# defi_schutz.net
KiCad netlist of a schematic drawn in EAGLE
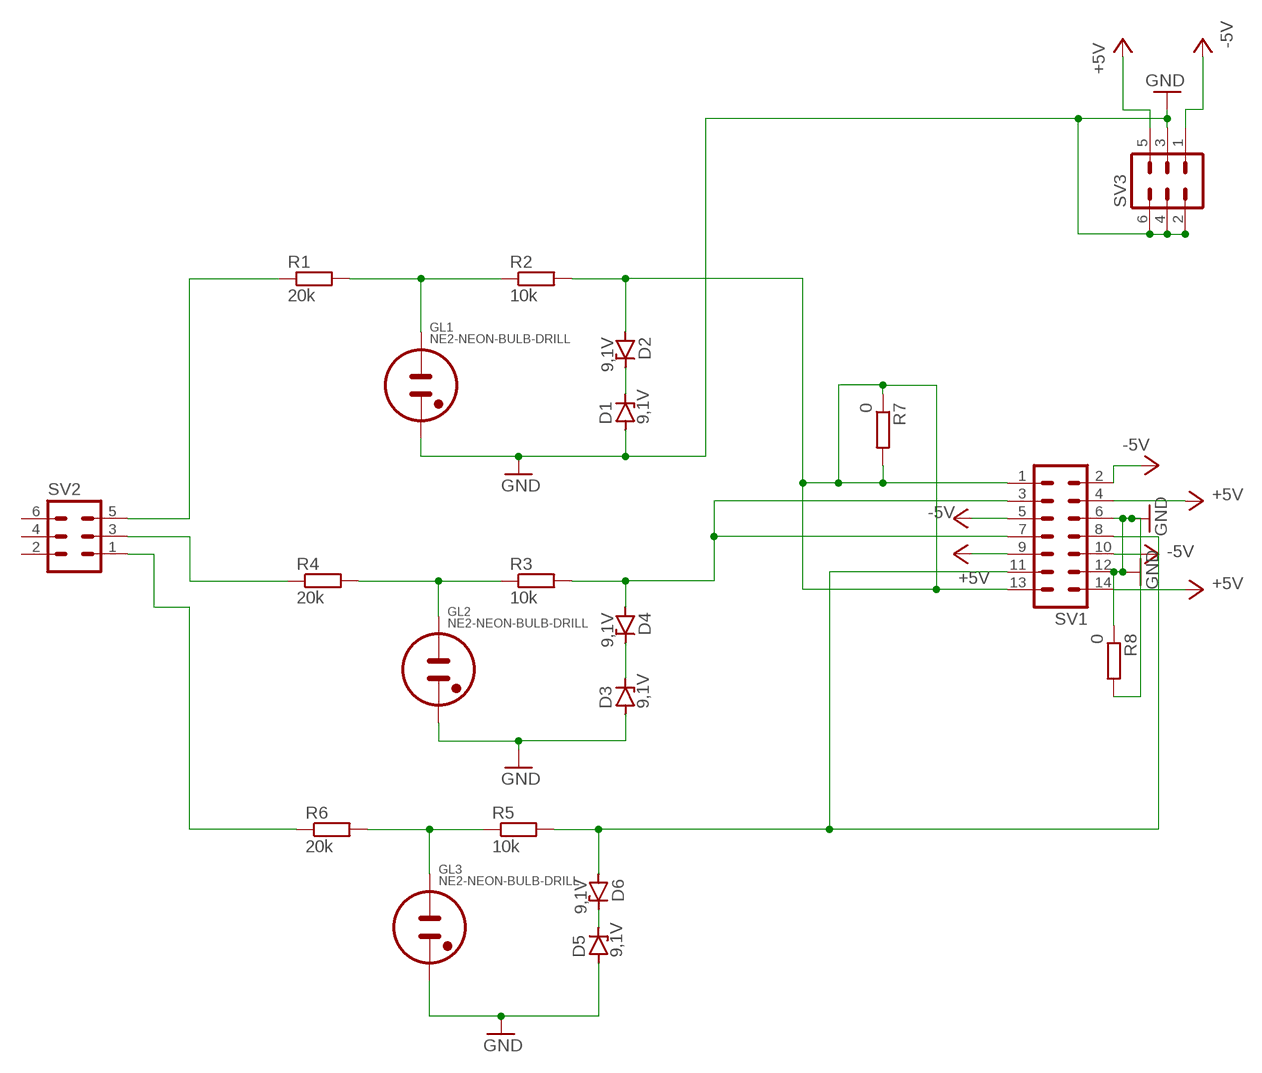
[diagram p0: schematic, sheet 1]

(export (version "E")
  (design (tool "Eeschema 10.0.6"))
  (components
    (comp (ref "D1")
      (value "9,1V")
      (footprint "eagle-import:DO41Z10")
      (libsource (lib "eagle-import") (part "1N4728"))
    )
    (comp (ref "D2")
      (value "9,1V")
      (footprint "eagle-import:DO41Z10")
      (libsource (lib "eagle-import") (part "1N4728"))
    )
    (comp (ref "D3")
      (value "9,1V")
      (footprint "eagle-import:DO41Z10")
      (libsource (lib "eagle-import") (part "1N4728"))
    )
    (comp (ref "D4")
      (value "9,1V")
      (footprint "eagle-import:DO41Z10")
      (libsource (lib "eagle-import") (part "1N4728"))
    )
    (comp (ref "D5")
      (value "9,1V")
      (footprint "eagle-import:DO41Z10")
      (libsource (lib "eagle-import") (part "1N4728"))
    )
    (comp (ref "D6")
      (value "9,1V")
      (footprint "eagle-import:DO41Z10")
      (libsource (lib "eagle-import") (part "1N4728"))
    )
    (comp (ref "GL1")
      (value "NE2-NEON-BULB-DRILL")
      (footprint "eagle-import:NE2-NEON-BULB-DRILL")
      (libsource (lib "eagle-import") (part "NE2-NEON-BULB-DRILL"))
    )
    (comp (ref "GL2")
      (value "NE2-NEON-BULB-DRILL")
      (footprint "eagle-import:NE2-NEON-BULB-DRILL")
      (libsource (lib "eagle-import") (part "NE2-NEON-BULB-DRILL"))
    )
    (comp (ref "GL3")
      (value "NE2-NEON-BULB-DRILL")
      (footprint "eagle-import:NE2-NEON-BULB-DRILL")
      (libsource (lib "eagle-import") (part "NE2-NEON-BULB-DRILL"))
    )
    (comp (ref "R1")
      (value "20k")
      (footprint "eagle-import:0207_10")
      (libsource (lib "eagle-import") (part "R-EU_0207/10"))
    )
    (comp (ref "R2")
      (value "10k")
      (footprint "eagle-import:0207_10")
      (libsource (lib "eagle-import") (part "R-EU_0207/10"))
    )
    (comp (ref "R3")
      (value "10k")
      (footprint "eagle-import:0207_10")
      (libsource (lib "eagle-import") (part "R-EU_0207/10"))
    )
    (comp (ref "R4")
      (value "20k")
      (footprint "eagle-import:0207_10")
      (libsource (lib "eagle-import") (part "R-EU_0207/10"))
    )
    (comp (ref "R5")
      (value "10k")
      (footprint "eagle-import:0207_10")
      (libsource (lib "eagle-import") (part "R-EU_0207/10"))
    )
    (comp (ref "R6")
      (value "20k")
      (footprint "eagle-import:0207_10")
      (libsource (lib "eagle-import") (part "R-EU_0207/10"))
    )
    (comp (ref "R7")
      (value "0")
      (footprint "eagle-import:0207_15")
      (libsource (lib "eagle-import") (part "R-EU_0207/15"))
    )
    (comp (ref "R8")
      (value "0")
      (footprint "eagle-import:0207_15")
      (libsource (lib "eagle-import") (part "R-EU_0207/15"))
    )
    (comp (ref "SV1")
      (value "ML14L")
      (footprint "eagle-import:ML14L")
      (libsource (lib "eagle-import") (part "ML14L"))
    )
    (comp (ref "SV2")
      (value "ML6L")
      (footprint "eagle-import:ML6L")
      (libsource (lib "eagle-import") (part "ML6L"))
    )
    (comp (ref "SV3")
      (value "ML6L")
      (footprint "eagle-import:ML6L")
      (libsource (lib "eagle-import") (part "ML6L"))
    )
  )
  (nets
    (net (code "1") (name "+5V") (class "Default")
      (node (ref "SV1") (pin "14") (pinfunction "14_14") (pintype "passive"))
      (node (ref "SV1") (pin "4") (pinfunction "4_4") (pintype "passive"))
      (node (ref "SV1") (pin "9") (pinfunction "9_9") (pintype "passive"))
      (node (ref "SV3") (pin "5") (pinfunction "5_5") (pintype "passive"))
    )
    (net (code "2") (name "-5V") (class "Default")
      (node (ref "SV1") (pin "10") (pinfunction "10_10") (pintype "passive"))
      (node (ref "SV1") (pin "2") (pinfunction "2_2") (pintype "passive"))
      (node (ref "SV1") (pin "5") (pinfunction "5_5") (pintype "passive"))
      (node (ref "SV3") (pin "1") (pinfunction "1_1") (pintype "passive"))
    )
    (net (code "3") (name "GND") (class "Default")
      (node (ref "D1") (pin "A") (pinfunction "A_A") (pintype "passive"))
      (node (ref "D3") (pin "A") (pinfunction "A_A") (pintype "passive"))
      (node (ref "D5") (pin "A") (pinfunction "A_A") (pintype "passive"))
      (node (ref "GL1") (pin "2") (pinfunction "A1_2") (pintype "passive"))
      (node (ref "GL2") (pin "2") (pinfunction "A1_2") (pintype "passive"))
      (node (ref "GL3") (pin "2") (pinfunction "A1_2") (pintype "passive"))
      (node (ref "R8") (pin "1") (pinfunction "1_1") (pintype "passive"))
      (node (ref "R8") (pin "2") (pinfunction "2_2") (pintype "passive"))
      (node (ref "SV1") (pin "12") (pinfunction "12_12") (pintype "passive"))
      (node (ref "SV1") (pin "6") (pinfunction "6_6") (pintype "passive"))
      (node (ref "SV3") (pin "2") (pinfunction "2_2") (pintype "passive"))
      (node (ref "SV3") (pin "3") (pinfunction "3_3") (pintype "passive"))
      (node (ref "SV3") (pin "4") (pinfunction "4_4") (pintype "passive"))
      (node (ref "SV3") (pin "6") (pinfunction "6_6") (pintype "passive"))
    )
    (net (code "4") (name "Net-(D1-PadC)") (class "Default")
      (node (ref "D1") (pin "C") (pinfunction "C_C") (pintype "passive"))
      (node (ref "D2") (pin "C") (pinfunction "C_C") (pintype "passive"))
    )
    (net (code "5") (name "Net-(D2-PadA)") (class "Default")
      (node (ref "D2") (pin "A") (pinfunction "A_A") (pintype "passive"))
      (node (ref "R2") (pin "2") (pinfunction "2_2") (pintype "passive"))
      (node (ref "R7") (pin "1") (pinfunction "1_1") (pintype "passive"))
      (node (ref "R7") (pin "2") (pinfunction "2_2") (pintype "passive"))
      (node (ref "SV1") (pin "1") (pinfunction "1_1") (pintype "passive"))
      (node (ref "SV1") (pin "13") (pinfunction "13_13") (pintype "passive"))
    )
    (net (code "6") (name "Net-(D3-PadC)") (class "Default")
      (node (ref "D3") (pin "C") (pinfunction "C_C") (pintype "passive"))
      (node (ref "D4") (pin "C") (pinfunction "C_C") (pintype "passive"))
    )
    (net (code "7") (name "Net-(D4-PadA)") (class "Default")
      (node (ref "D4") (pin "A") (pinfunction "A_A") (pintype "passive"))
      (node (ref "R3") (pin "2") (pinfunction "2_2") (pintype "passive"))
      (node (ref "SV1") (pin "3") (pinfunction "3_3") (pintype "passive"))
      (node (ref "SV1") (pin "7") (pinfunction "7_7") (pintype "passive"))
    )
    (net (code "8") (name "Net-(D5-PadC)") (class "Default")
      (node (ref "D5") (pin "C") (pinfunction "C_C") (pintype "passive"))
      (node (ref "D6") (pin "C") (pinfunction "C_C") (pintype "passive"))
    )
    (net (code "9") (name "Net-(D6-PadA)") (class "Default")
      (node (ref "D6") (pin "A") (pinfunction "A_A") (pintype "passive"))
      (node (ref "R5") (pin "2") (pinfunction "2_2") (pintype "passive"))
      (node (ref "SV1") (pin "11") (pinfunction "11_11") (pintype "passive"))
      (node (ref "SV1") (pin "8") (pinfunction "8_8") (pintype "passive"))
    )
    (net (code "10") (name "Net-(GL1-A)") (class "Default")
      (node (ref "GL1") (pin "1") (pinfunction "A_1") (pintype "passive"))
      (node (ref "R1") (pin "2") (pinfunction "2_2") (pintype "passive"))
      (node (ref "R2") (pin "1") (pinfunction "1_1") (pintype "passive"))
    )
    (net (code "11") (name "Net-(GL2-A)") (class "Default")
      (node (ref "GL2") (pin "1") (pinfunction "A_1") (pintype "passive"))
      (node (ref "R3") (pin "1") (pinfunction "1_1") (pintype "passive"))
      (node (ref "R4") (pin "2") (pinfunction "2_2") (pintype "passive"))
    )
    (net (code "12") (name "Net-(GL3-A)") (class "Default")
      (node (ref "GL3") (pin "1") (pinfunction "A_1") (pintype "passive"))
      (node (ref "R5") (pin "1") (pinfunction "1_1") (pintype "passive"))
      (node (ref "R6") (pin "2") (pinfunction "2_2") (pintype "passive"))
    )
    (net (code "13") (name "Net-(R1-Pad1)") (class "Default")
      (node (ref "R1") (pin "1") (pinfunction "1_1") (pintype "passive"))
      (node (ref "SV2") (pin "5") (pinfunction "5_5") (pintype "passive"))
    )
    (net (code "14") (name "Net-(R4-Pad1)") (class "Default")
      (node (ref "R4") (pin "1") (pinfunction "1_1") (pintype "passive"))
      (node (ref "SV2") (pin "3") (pinfunction "3_3") (pintype "passive"))
    )
    (net (code "15") (name "Net-(R6-Pad1)") (class "Default")
      (node (ref "R6") (pin "1") (pinfunction "1_1") (pintype "passive"))
      (node (ref "SV2") (pin "1") (pinfunction "1_1") (pintype "passive"))
    )
    (net (code "16") (name "unconnected-(SV2-Pad2)") (class "Default")
      (node (ref "SV2") (pin "2") (pinfunction "2_2") (pintype "passive"))
    )
    (net (code "17") (name "unconnected-(SV2-Pad4)") (class "Default")
      (node (ref "SV2") (pin "4") (pinfunction "4_4") (pintype "passive"))
    )
    (net (code "18") (name "unconnected-(SV2-Pad6)") (class "Default")
      (node (ref "SV2") (pin "6") (pinfunction "6_6") (pintype "passive"))
    )
  )
)
